# Buton_Unit.net
KiCad netlist of a schematic drawn in Altium Designer
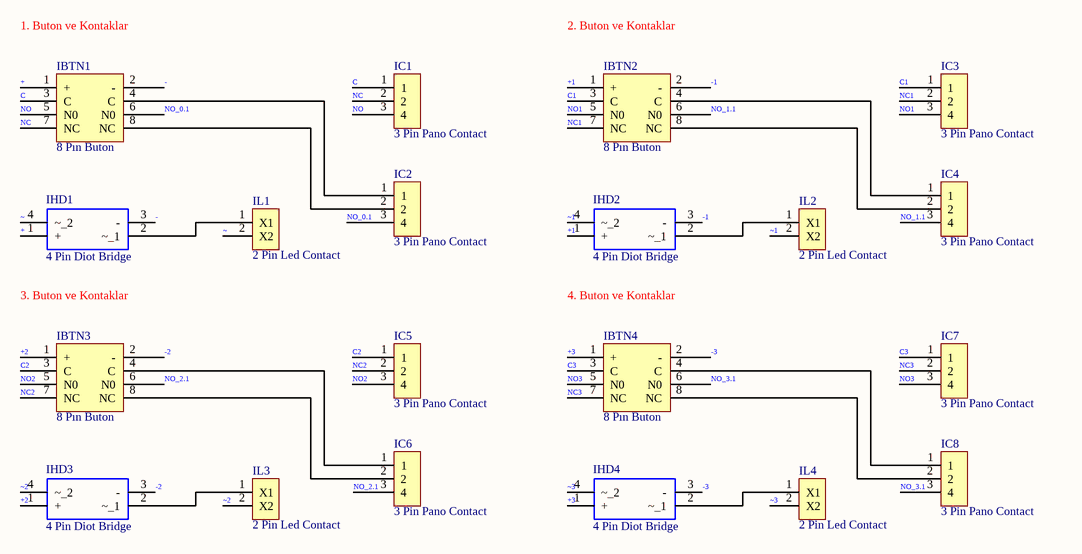
[diagram p0: Buton_Unit.SchDoc]

(export (version "E")
  (design (tool "Eeschema 10.0.6"))
  (components
    (comp (ref "IBTN1")
      (value "8 Pın Buton")
      (footprint "8_Pin_Buton")
      (libsource (lib "STANDART KUMANDA PANELİ") (part "PBL16_AC_DC 24V_IP65"))
    )
    (comp (ref "IBTN2")
      (value "8 Pın Buton")
      (footprint "8_Pin_Buton")
      (libsource (lib "STANDART KUMANDA PANELİ") (part "PBL16_AC_DC 24V_IP65"))
    )
    (comp (ref "IBTN3")
      (value "8 Pın Buton")
      (footprint "8_Pin_Buton")
      (libsource (lib "STANDART KUMANDA PANELİ") (part "PBL16_AC_DC 24V_IP65"))
    )
    (comp (ref "IBTN4")
      (value "8 Pın Buton")
      (footprint "8_Pin_Buton")
      (libsource (lib "STANDART KUMANDA PANELİ") (part "PBL16_AC_DC 24V_IP65"))
    )
    (comp (ref "IC1")
      (value "3 Pin Pano Contact")
      (footprint "Standart Kumanda Paneli:Contact")
      (libsource (lib "STANDART KUMANDA PANELİ") (part "Contact"))
    )
    (comp (ref "IC2")
      (value "3 Pin Pano Contact")
      (footprint "Standart Kumanda Paneli:Contact")
      (libsource (lib "STANDART KUMANDA PANELİ") (part "Contact"))
    )
    (comp (ref "IC3")
      (value "3 Pin Pano Contact")
      (footprint "Standart Kumanda Paneli:Contact")
      (libsource (lib "STANDART KUMANDA PANELİ") (part "Contact"))
    )
    (comp (ref "IC4")
      (value "3 Pin Pano Contact")
      (footprint "Standart Kumanda Paneli:Contact")
      (libsource (lib "STANDART KUMANDA PANELİ") (part "Contact"))
    )
    (comp (ref "IC5")
      (value "3 Pin Pano Contact")
      (footprint "Standart Kumanda Paneli:Contact")
      (libsource (lib "STANDART KUMANDA PANELİ") (part "Contact"))
    )
    (comp (ref "IC6")
      (value "3 Pin Pano Contact")
      (footprint "Standart Kumanda Paneli:Contact")
      (libsource (lib "STANDART KUMANDA PANELİ") (part "Contact"))
    )
    (comp (ref "IC7")
      (value "3 Pin Pano Contact")
      (footprint "Standart Kumanda Paneli:Contact")
      (libsource (lib "STANDART KUMANDA PANELİ") (part "Contact"))
    )
    (comp (ref "IC8")
      (value "3 Pin Pano Contact")
      (footprint "Standart Kumanda Paneli:Contact")
      (libsource (lib "STANDART KUMANDA PANELİ") (part "Contact"))
    )
    (comp (ref "IHD1")
      (value "4 Pin Diot Bridge")
      (footprint "Standart Kumanda Paneli:W10M")
      (libsource (lib "STANDART KUMANDA PANELİ") (part "W10M"))
    )
    (comp (ref "IHD2")
      (value "4 Pin Diot Bridge")
      (footprint "Standart Kumanda Paneli:W10M")
      (libsource (lib "STANDART KUMANDA PANELİ") (part "W10M"))
    )
    (comp (ref "IHD3")
      (value "4 Pin Diot Bridge")
      (footprint "Standart Kumanda Paneli:W10M")
      (libsource (lib "STANDART KUMANDA PANELİ") (part "W10M"))
    )
    (comp (ref "IHD4")
      (value "4 Pin Diot Bridge")
      (footprint "Standart Kumanda Paneli:W10M")
      (libsource (lib "STANDART KUMANDA PANELİ") (part "W10M"))
    )
    (comp (ref "IL1")
      (value "2 Pin Led Contact")
      (footprint "Standart Kumanda Paneli:LED_Contact")
      (libsource (lib "STANDART KUMANDA PANELİ") (part "LED_Contact"))
    )
    (comp (ref "IL2")
      (value "2 Pin Led Contact")
      (footprint "Standart Kumanda Paneli:LED_Contact")
      (libsource (lib "STANDART KUMANDA PANELİ") (part "LED_Contact"))
    )
    (comp (ref "IL3")
      (value "2 Pin Led Contact")
      (footprint "Standart Kumanda Paneli:LED_Contact")
      (libsource (lib "STANDART KUMANDA PANELİ") (part "LED_Contact"))
    )
    (comp (ref "IL4")
      (value "2 Pin Led Contact")
      (footprint "Standart Kumanda Paneli:LED_Contact")
      (libsource (lib "STANDART KUMANDA PANELİ") (part "LED_Contact"))
    )
  )
  (nets
    (net (code "1") (name "/+") (class "Default")
      (node (ref "IBTN1") (pin "1") (pinfunction "+_1") (pintype "passive"))
      (node (ref "IHD1") (pin "1") (pinfunction "+_1") (pintype "passive"))
    )
    (net (code "2") (name "/+1") (class "Default")
      (node (ref "IBTN2") (pin "1") (pinfunction "+_1") (pintype "passive"))
      (node (ref "IHD2") (pin "1") (pinfunction "+_1") (pintype "passive"))
    )
    (net (code "3") (name "/+2") (class "Default")
      (node (ref "IBTN3") (pin "1") (pinfunction "+_1") (pintype "passive"))
      (node (ref "IHD3") (pin "1") (pinfunction "+_1") (pintype "passive"))
    )
    (net (code "4") (name "/+3") (class "Default")
      (node (ref "IBTN4") (pin "1") (pinfunction "+_1") (pintype "passive"))
      (node (ref "IHD4") (pin "1") (pinfunction "+_1") (pintype "passive"))
    )
    (net (code "5") (name "/-") (class "Default")
      (node (ref "IBTN1") (pin "2") (pinfunction "-_2") (pintype "passive"))
      (node (ref "IHD1") (pin "3") (pinfunction "-_3") (pintype "passive"))
    )
    (net (code "6") (name "/-1") (class "Default")
      (node (ref "IBTN2") (pin "2") (pinfunction "-_2") (pintype "passive"))
      (node (ref "IHD2") (pin "3") (pinfunction "-_3") (pintype "passive"))
    )
    (net (code "7") (name "/-2") (class "Default")
      (node (ref "IBTN3") (pin "2") (pinfunction "-_2") (pintype "passive"))
      (node (ref "IHD3") (pin "3") (pinfunction "-_3") (pintype "passive"))
    )
    (net (code "8") (name "/-3") (class "Default")
      (node (ref "IBTN4") (pin "2") (pinfunction "-_2") (pintype "passive"))
      (node (ref "IHD4") (pin "3") (pinfunction "-_3") (pintype "passive"))
    )
    (net (code "9") (name "/C") (class "Default")
      (node (ref "IBTN1") (pin "3") (pinfunction "C_3") (pintype "passive"))
      (node (ref "IC1") (pin "1") (pinfunction "1_1") (pintype "passive"))
    )
    (net (code "10") (name "/C1") (class "Default")
      (node (ref "IBTN2") (pin "3") (pinfunction "C_3") (pintype "passive"))
      (node (ref "IC3") (pin "1") (pinfunction "1_1") (pintype "passive"))
    )
    (net (code "11") (name "/C2") (class "Default")
      (node (ref "IBTN3") (pin "3") (pinfunction "C_3") (pintype "passive"))
      (node (ref "IC5") (pin "1") (pinfunction "1_1") (pintype "passive"))
    )
    (net (code "12") (name "/C3") (class "Default")
      (node (ref "IBTN4") (pin "3") (pinfunction "C_3") (pintype "passive"))
      (node (ref "IC7") (pin "1") (pinfunction "1_1") (pintype "passive"))
    )
    (net (code "13") (name "/NC") (class "Default")
      (node (ref "IBTN1") (pin "7") (pinfunction "NC_7") (pintype "passive"))
      (node (ref "IC1") (pin "2") (pinfunction "2_2") (pintype "passive"))
    )
    (net (code "14") (name "/NC1") (class "Default")
      (node (ref "IBTN2") (pin "7") (pinfunction "NC_7") (pintype "passive"))
      (node (ref "IC3") (pin "2") (pinfunction "2_2") (pintype "passive"))
    )
    (net (code "15") (name "/NC2") (class "Default")
      (node (ref "IBTN3") (pin "7") (pinfunction "NC_7") (pintype "passive"))
      (node (ref "IC5") (pin "2") (pinfunction "2_2") (pintype "passive"))
    )
    (net (code "16") (name "/NC3") (class "Default")
      (node (ref "IBTN4") (pin "7") (pinfunction "NC_7") (pintype "passive"))
      (node (ref "IC7") (pin "2") (pinfunction "2_2") (pintype "passive"))
    )
    (net (code "17") (name "/NO") (class "Default")
      (node (ref "IBTN1") (pin "5") (pinfunction "N0_5") (pintype "passive"))
      (node (ref "IC1") (pin "3") (pinfunction "4_3") (pintype "passive"))
    )
    (net (code "18") (name "/NO1") (class "Default")
      (node (ref "IBTN2") (pin "5") (pinfunction "N0_5") (pintype "passive"))
      (node (ref "IC3") (pin "3") (pinfunction "4_3") (pintype "passive"))
    )
    (net (code "19") (name "/NO2") (class "Default")
      (node (ref "IBTN3") (pin "5") (pinfunction "N0_5") (pintype "passive"))
      (node (ref "IC5") (pin "3") (pinfunction "4_3") (pintype "passive"))
    )
    (net (code "20") (name "/NO3") (class "Default")
      (node (ref "IBTN4") (pin "5") (pinfunction "N0_5") (pintype "passive"))
      (node (ref "IC7") (pin "3") (pinfunction "4_3") (pintype "passive"))
    )
    (net (code "21") (name "/NO_0.1") (class "Default")
      (node (ref "IBTN1") (pin "6") (pinfunction "N0_6") (pintype "passive"))
      (node (ref "IC2") (pin "3") (pinfunction "4_3") (pintype "passive"))
    )
    (net (code "22") (name "/NO_1.1") (class "Default")
      (node (ref "IBTN2") (pin "6") (pinfunction "N0_6") (pintype "passive"))
      (node (ref "IC4") (pin "3") (pinfunction "4_3") (pintype "passive"))
    )
    (net (code "23") (name "/NO_2.1") (class "Default")
      (node (ref "IBTN3") (pin "6") (pinfunction "N0_6") (pintype "passive"))
      (node (ref "IC6") (pin "3") (pinfunction "4_3") (pintype "passive"))
    )
    (net (code "24") (name "/NO_3.1") (class "Default")
      (node (ref "IBTN4") (pin "6") (pinfunction "N0_6") (pintype "passive"))
      (node (ref "IC8") (pin "3") (pinfunction "4_3") (pintype "passive"))
    )
    (net (code "25") (name "/~") (class "Default")
      (node (ref "IHD1") (pin "4") (pinfunction "~_2_4") (pintype "passive"))
      (node (ref "IL1") (pin "2") (pinfunction "X2_2") (pintype "passive"))
    )
    (net (code "26") (name "/~1") (class "Default")
      (node (ref "IHD2") (pin "4") (pinfunction "~_2_4") (pintype "passive"))
      (node (ref "IL2") (pin "2") (pinfunction "X2_2") (pintype "passive"))
    )
    (net (code "27") (name "/~2") (class "Default")
      (node (ref "IHD3") (pin "4") (pinfunction "~_2_4") (pintype "passive"))
      (node (ref "IL3") (pin "2") (pinfunction "X2_2") (pintype "passive"))
    )
    (net (code "28") (name "/~3") (class "Default")
      (node (ref "IHD4") (pin "4") (pinfunction "~_2_4") (pintype "passive"))
      (node (ref "IL4") (pin "2") (pinfunction "X2_2") (pintype "passive"))
    )
    (net (code "29") (name "Net-(IBTN1-C-Pad4)") (class "Default")
      (node (ref "IBTN1") (pin "4") (pinfunction "C_4") (pintype "passive"))
      (node (ref "IC2") (pin "1") (pinfunction "1_1") (pintype "passive"))
    )
    (net (code "30") (name "Net-(IBTN1-NC-Pad8)") (class "Default")
      (node (ref "IBTN1") (pin "8") (pinfunction "NC_8") (pintype "passive"))
      (node (ref "IC2") (pin "2") (pinfunction "2_2") (pintype "passive"))
    )
    (net (code "31") (name "Net-(IBTN2-C-Pad4)") (class "Default")
      (node (ref "IBTN2") (pin "4") (pinfunction "C_4") (pintype "passive"))
      (node (ref "IC4") (pin "1") (pinfunction "1_1") (pintype "passive"))
    )
    (net (code "32") (name "Net-(IBTN2-NC-Pad8)") (class "Default")
      (node (ref "IBTN2") (pin "8") (pinfunction "NC_8") (pintype "passive"))
      (node (ref "IC4") (pin "2") (pinfunction "2_2") (pintype "passive"))
    )
    (net (code "33") (name "Net-(IBTN3-C-Pad4)") (class "Default")
      (node (ref "IBTN3") (pin "4") (pinfunction "C_4") (pintype "passive"))
      (node (ref "IC6") (pin "1") (pinfunction "1_1") (pintype "passive"))
    )
    (net (code "34") (name "Net-(IBTN3-NC-Pad8)") (class "Default")
      (node (ref "IBTN3") (pin "8") (pinfunction "NC_8") (pintype "passive"))
      (node (ref "IC6") (pin "2") (pinfunction "2_2") (pintype "passive"))
    )
    (net (code "35") (name "Net-(IBTN4-C-Pad4)") (class "Default")
      (node (ref "IBTN4") (pin "4") (pinfunction "C_4") (pintype "passive"))
      (node (ref "IC8") (pin "1") (pinfunction "1_1") (pintype "passive"))
    )
    (net (code "36") (name "Net-(IBTN4-NC-Pad8)") (class "Default")
      (node (ref "IBTN4") (pin "8") (pinfunction "NC_8") (pintype "passive"))
      (node (ref "IC8") (pin "2") (pinfunction "2_2") (pintype "passive"))
    )
    (net (code "37") (name "Net-(IHD1-~_1)") (class "Default")
      (node (ref "IHD1") (pin "2") (pinfunction "~_1_2") (pintype "passive"))
      (node (ref "IL1") (pin "1") (pinfunction "X1_1") (pintype "passive"))
    )
    (net (code "38") (name "Net-(IHD2-~_1)") (class "Default")
      (node (ref "IHD2") (pin "2") (pinfunction "~_1_2") (pintype "passive"))
      (node (ref "IL2") (pin "1") (pinfunction "X1_1") (pintype "passive"))
    )
    (net (code "39") (name "Net-(IHD3-~_1)") (class "Default")
      (node (ref "IHD3") (pin "2") (pinfunction "~_1_2") (pintype "passive"))
      (node (ref "IL3") (pin "1") (pinfunction "X1_1") (pintype "passive"))
    )
    (net (code "40") (name "Net-(IHD4-~_1)") (class "Default")
      (node (ref "IHD4") (pin "2") (pinfunction "~_1_2") (pintype "passive"))
      (node (ref "IL4") (pin "1") (pinfunction "X1_1") (pintype "passive"))
    )
  )
)
